# mLRStxtx.net
KiCad netlist of a schematic drawn in Altium Designer
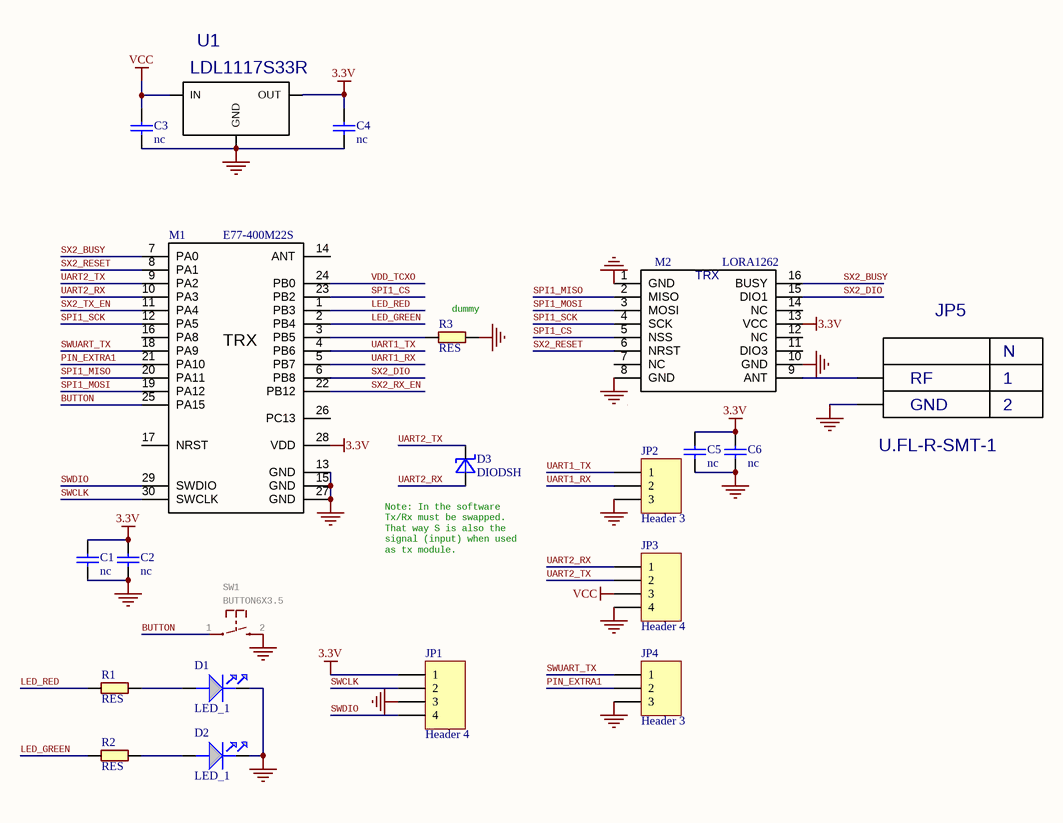
[diagram p0: mLRStxtx.SchDoc]

(export (version "E")
  (design (tool "Eeschema 10.0.6"))
  (components
    (comp (ref "C1")
      (value "nc")
      (footprint "C-0603")
      (fields (field (name "VOLTAGE") "50V"))
      (libsource (lib "LR1121EVM") (part "CAPN"))
    )
    (comp (ref "C2")
      (value "nc")
      (footprint "C-0603")
      (fields (field (name "VOLTAGE") "50V"))
      (libsource (lib "LR1121EVM") (part "CAPN"))
    )
    (comp (ref "C3")
      (value "nc")
      (footprint "C-0805")
      (fields (field (name "VOLTAGE") "50V"))
      (libsource (lib "LR1121EVM") (part "CAPN"))
    )
    (comp (ref "C4")
      (value "nc")
      (footprint "C-0805")
      (fields (field (name "VOLTAGE") "50V"))
      (libsource (lib "LR1121EVM") (part "CAPN"))
    )
    (comp (ref "C5")
      (value "nc")
      (footprint "C-0603")
      (fields (field (name "VOLTAGE") "50V"))
      (libsource (lib "LR1121EVM") (part "CAPN"))
    )
    (comp (ref "C6")
      (value "nc")
      (footprint "C-0603")
      (fields (field (name "VOLTAGE") "50V"))
      (libsource (lib "LR1121EVM") (part "CAPN"))
    )
    (comp (ref "D1") (value "LED_1") (footprint "LED_0805") (libsource (lib "Diodes") (part "LED_1")))
    (comp (ref "D2") (value "LED_1") (footprint "LED_0805") (libsource (lib "Diodes") (part "LED_1")))
    (comp (ref "D3") (value "DIODSH") (footprint "SOD-323") (libsource (lib "Diodes") (part "DIODSH")))
    (comp (ref "JP1")
      (value "Header 4")
      (footprint "HDR1X4")
      (description "Header, 4-Pin")
      (fields (field (name "PUBLISHER") "Altium Limited"))
      (libsource (lib "Miscellaneous Connectors") (part "Header 4"))
    )
    (comp (ref "JP2")
      (value "Header 3")
      (footprint "HDR1X3")
      (description "Header, 3-Pin")
      (fields (field (name "PUBLISHER") "Altium Limited"))
      (libsource (lib "Miscellaneous Connectors") (part "Header 3"))
    )
    (comp (ref "JP3")
      (value "Header 4")
      (footprint "HDR1X4")
      (description "Header, 4-Pin")
      (fields (field (name "PUBLISHER") "Altium Limited"))
      (libsource (lib "Miscellaneous Connectors") (part "Header 4"))
    )
    (comp (ref "JP4")
      (value "Header 3")
      (footprint "HDR1X3")
      (description "Header, 3-Pin")
      (fields (field (name "PUBLISHER") "Altium Limited"))
      (libsource (lib "Miscellaneous Connectors") (part "Header 3"))
    )
    (comp (ref "JP5")
      (value "U.FL-R-SMT-1")
      (footprint "U.FL-R-SMT-1")
      (libsource (lib "E2002") (part "U.FL-R-SMT-1"))
    )
    (comp (ref "M1")
      (value "E77-400M22S")
      (footprint "E77XX-M22")
      (libsource (lib "LR1121EVM") (part "E77-400M22S"))
    )
    (comp (ref "M2")
      (value "LORA1262")
      (footprint "LGA16_LORA1280")
      (libsource (lib "LR1121EVM") (part "LORA1262"))
    )
    (comp (ref "R1") (value "RES") (footprint "R-0603") (libsource (lib "LR1121EVM") (part "RES")))
    (comp (ref "R2") (value "RES") (footprint "R-0603") (libsource (lib "LR1121EVM") (part "RES")))
    (comp (ref "R3") (value "RES") (footprint "R-0603") (libsource (lib "LR1121EVM") (part "RES")))
    (comp (ref "SW1")
      (value "BUTTON6X3.5")
      (footprint "BUTTON-THT")
      (fields (field (name "LIBRARYNAME") "# stdlib"))
      (libsource (lib "# stdlib") (part "BUTTON6X3.5"))
    )
    (comp (ref "U1")
      (value "LDL1117S33R")
      (footprint "SOT223")
      (libsource (lib "E2002") (part "LDL1117S33R"))
    )
  )
  (nets
    (net (code "1") (name "/BUTTON") (class "Default")
      (node (ref "M1") (pin "25") (pinfunction "PA15_25") (pintype "passive"))
      (node (ref "SW1") (pin "1") (pinfunction "1_1") (pintype "passive"))
    )
    (net (code "2") (name "/LED_GREEN") (class "Default")
      (node (ref "M1") (pin "2") (pinfunction "PB4_2") (pintype "passive"))
      (node (ref "R2") (pin "2") (pinfunction "2_2") (pintype "passive"))
    )
    (net (code "3") (name "/LED_RED") (class "Default")
      (node (ref "M1") (pin "1") (pinfunction "PB3_1") (pintype "passive"))
      (node (ref "R1") (pin "2") (pinfunction "2_2") (pintype "passive"))
    )
    (net (code "4") (name "/PIN_EXTRA1") (class "Default")
      (node (ref "JP4") (pin "2") (pinfunction "2_2") (pintype "passive"))
      (node (ref "M1") (pin "21") (pinfunction "PA10_21") (pintype "passive"))
    )
    (net (code "5") (name "/SPI1_CS") (class "Default")
      (node (ref "M1") (pin "23") (pinfunction "PB2_23") (pintype "passive"))
      (node (ref "M2") (pin "5") (pinfunction "NSS_5") (pintype "passive"))
    )
    (net (code "6") (name "/SPI1_MISO") (class "Default")
      (node (ref "M1") (pin "20") (pinfunction "PA11_20") (pintype "passive"))
      (node (ref "M2") (pin "2") (pinfunction "MISO_2") (pintype "passive"))
    )
    (net (code "7") (name "/SPI1_MOSI") (class "Default")
      (node (ref "M1") (pin "19") (pinfunction "PA12_19") (pintype "passive"))
      (node (ref "M2") (pin "3") (pinfunction "MOSI_3") (pintype "passive"))
    )
    (net (code "8") (name "/SPI1_SCK") (class "Default")
      (node (ref "M1") (pin "12") (pinfunction "PA5_12") (pintype "passive"))
      (node (ref "M2") (pin "4") (pinfunction "SCK_4") (pintype "passive"))
    )
    (net (code "9") (name "/SWCLK") (class "Default")
      (node (ref "JP1") (pin "2") (pinfunction "2_2") (pintype "passive"))
      (node (ref "M1") (pin "30") (pinfunction "SWCLK_30") (pintype "passive"))
    )
    (net (code "10") (name "/SWDIO") (class "Default")
      (node (ref "JP1") (pin "4") (pinfunction "4_4") (pintype "passive"))
      (node (ref "M1") (pin "29") (pinfunction "SWDIO_29") (pintype "passive"))
    )
    (net (code "11") (name "/SWUART_TX") (class "Default")
      (node (ref "JP4") (pin "1") (pinfunction "1_1") (pintype "passive"))
      (node (ref "M1") (pin "18") (pinfunction "PA9_18") (pintype "passive"))
    )
    (net (code "12") (name "/SX2_BUSY") (class "Default")
      (node (ref "M1") (pin "7") (pinfunction "PA0_7") (pintype "passive"))
      (node (ref "M2") (pin "16") (pinfunction "BUSY_16") (pintype "passive"))
    )
    (net (code "13") (name "/SX2_DIO") (class "Default")
      (node (ref "M1") (pin "6") (pinfunction "PB8_6") (pintype "passive"))
      (node (ref "M2") (pin "15") (pinfunction "DIO1_15") (pintype "passive"))
    )
    (net (code "14") (name "/SX2_RESET") (class "Default")
      (node (ref "M1") (pin "8") (pinfunction "PA1_8") (pintype "passive"))
      (node (ref "M2") (pin "6") (pinfunction "NRST_6") (pintype "passive"))
    )
    (net (code "15") (name "/SX2_RX_EN") (class "Default")
      (node (ref "M1") (pin "22") (pinfunction "PB12_22") (pintype "passive"))
    )
    (net (code "16") (name "/SX2_TX_EN") (class "Default")
      (node (ref "M1") (pin "11") (pinfunction "PA4_11") (pintype "passive"))
    )
    (net (code "17") (name "/UART1_RX") (class "Default")
      (node (ref "JP2") (pin "2") (pinfunction "2_2") (pintype "passive"))
      (node (ref "M1") (pin "5") (pinfunction "PB7_5") (pintype "passive"))
    )
    (net (code "18") (name "/UART1_TX") (class "Default")
      (node (ref "JP2") (pin "1") (pinfunction "1_1") (pintype "passive"))
      (node (ref "M1") (pin "4") (pinfunction "PB6_4") (pintype "passive"))
    )
    (net (code "19") (name "/UART2_RX") (class "Default")
      (node (ref "D3") (pin "1") (pinfunction "1_1") (pintype "passive"))
      (node (ref "JP3") (pin "1") (pinfunction "1_1") (pintype "passive"))
      (node (ref "M1") (pin "10") (pinfunction "PA3_10") (pintype "passive"))
    )
    (net (code "20") (name "/UART2_TX") (class "Default")
      (node (ref "D3") (pin "2") (pinfunction "2_2") (pintype "passive"))
      (node (ref "JP3") (pin "2") (pinfunction "2_2") (pintype "passive"))
      (node (ref "M1") (pin "9") (pinfunction "PA2_9") (pintype "passive"))
    )
    (net (code "21") (name "/VDD_TCXO") (class "Default")
      (node (ref "M1") (pin "24") (pinfunction "PB0_24") (pintype "passive"))
    )
    (net (code "22") (name "3.3V") (class "Default")
      (node (ref "C1") (pin "1") (pinfunction "1_1") (pintype "passive"))
      (node (ref "C2") (pin "1") (pinfunction "1_1") (pintype "passive"))
      (node (ref "C4") (pin "1") (pinfunction "1_1") (pintype "passive"))
      (node (ref "C5") (pin "1") (pinfunction "1_1") (pintype "passive"))
      (node (ref "C6") (pin "1") (pinfunction "1_1") (pintype "passive"))
      (node (ref "JP1") (pin "1") (pinfunction "1_1") (pintype "passive"))
      (node (ref "M1") (pin "28") (pinfunction "VDD_28") (pintype "passive"))
      (node (ref "M2") (pin "13") (pinfunction "VCC_13") (pintype "passive"))
      (node (ref "U1") (pin "2") (pinfunction "OUT_2") (pintype "passive"))
    )
    (net (code "23") (name "GND") (class "Default")
      (node (ref "C1") (pin "2") (pinfunction "2_2") (pintype "passive"))
      (node (ref "C2") (pin "2") (pinfunction "2_2") (pintype "passive"))
      (node (ref "C3") (pin "2") (pinfunction "2_2") (pintype "passive"))
      (node (ref "C4") (pin "2") (pinfunction "2_2") (pintype "passive"))
      (node (ref "C5") (pin "2") (pinfunction "2_2") (pintype "passive"))
      (node (ref "C6") (pin "2") (pinfunction "2_2") (pintype "passive"))
      (node (ref "D1") (pin "K") (pinfunction "CATHODE_K") (pintype "passive"))
      (node (ref "D2") (pin "K") (pinfunction "CATHODE_K") (pintype "passive"))
      (node (ref "JP1") (pin "3") (pinfunction "3_3") (pintype "passive"))
      (node (ref "JP2") (pin "3") (pinfunction "3_3") (pintype "passive"))
      (node (ref "JP3") (pin "4") (pinfunction "4_4") (pintype "passive"))
      (node (ref "JP4") (pin "3") (pinfunction "3_3") (pintype "passive"))
      (node (ref "JP5") (pin "2") (pinfunction "2_2") (pintype "passive"))
      (node (ref "M1") (pin "13") (pinfunction "GND_13") (pintype "passive"))
      (node (ref "M1") (pin "15") (pinfunction "GND_15") (pintype "passive"))
      (node (ref "M1") (pin "27") (pinfunction "GND_27") (pintype "passive"))
      (node (ref "M2") (pin "1") (pinfunction "GND_1") (pintype "passive"))
      (node (ref "M2") (pin "10") (pinfunction "GND_10") (pintype "passive"))
      (node (ref "M2") (pin "8") (pinfunction "GND_8") (pintype "passive"))
      (node (ref "R3") (pin "1") (pinfunction "1_1") (pintype "passive"))
      (node (ref "SW1") (pin "2") (pinfunction "3_2") (pintype "passive"))
      (node (ref "U1") (pin "1") (pinfunction "GND_1") (pintype "passive"))
    )
    (net (code "24") (name "Net-(D1-ANODE)") (class "Default")
      (node (ref "D1") (pin "A") (pinfunction "ANODE_A") (pintype "passive"))
      (node (ref "R1") (pin "1") (pinfunction "1_1") (pintype "passive"))
    )
    (net (code "25") (name "Net-(D2-ANODE)") (class "Default")
      (node (ref "D2") (pin "A") (pinfunction "ANODE_A") (pintype "passive"))
      (node (ref "R2") (pin "1") (pinfunction "1_1") (pintype "passive"))
    )
    (net (code "26") (name "Net-(M1-PB5)") (class "Default")
      (node (ref "M1") (pin "3") (pinfunction "PB5_3") (pintype "passive"))
      (node (ref "R3") (pin "2") (pinfunction "2_2") (pintype "passive"))
    )
    (net (code "27") (name "Net-(M2-ANT)") (class "Default")
      (node (ref "JP5") (pin "1") (pinfunction "1_1") (pintype "passive"))
      (node (ref "M2") (pin "9") (pinfunction "ANT_9") (pintype "passive"))
    )
    (net (code "28") (name "VCC") (class "Default")
      (node (ref "C3") (pin "1") (pinfunction "1_1") (pintype "passive"))
      (node (ref "JP3") (pin "3") (pinfunction "3_3") (pintype "passive"))
      (node (ref "U1") (pin "3") (pinfunction "IN_3") (pintype "passive"))
    )
    (net (code "29") (name "unconnected-(M1-ANT-Pad14)") (class "Default")
      (node (ref "M1") (pin "14") (pinfunction "ANT_14") (pintype "passive"))
    )
    (net (code "30") (name "unconnected-(M1-NRST-Pad17)") (class "Default")
      (node (ref "M1") (pin "17") (pinfunction "NRST_17") (pintype "passive"))
    )
    (net (code "31") (name "unconnected-(M1-PA8-Pad16)") (class "Default")
      (node (ref "M1") (pin "16") (pinfunction "PA8_16") (pintype "passive"))
    )
    (net (code "32") (name "unconnected-(M1-PC13-Pad26)") (class "Default")
      (node (ref "M1") (pin "26") (pinfunction "PC13_26") (pintype "passive"))
    )
    (net (code "33") (name "unconnected-(M2-DIO3-Pad11)") (class "Default")
      (node (ref "M2") (pin "11") (pinfunction "DIO3_11") (pintype "passive"))
    )
    (net (code "34") (name "unconnected-(M2-NC-Pad7)") (class "Default")
      (node (ref "M2") (pin "7") (pinfunction "NC_7") (pintype "passive"))
    )
    (net (code "35") (name "unconnected-(M2-NC-Pad12)") (class "Default")
      (node (ref "M2") (pin "12") (pinfunction "NC_12") (pintype "passive"))
    )
    (net (code "36") (name "unconnected-(M2-NC-Pad14)") (class "Default")
      (node (ref "M2") (pin "14") (pinfunction "NC_14") (pintype "passive"))
    )
    (net (code "37") (name "unconnected-(U1-Pad4)") (class "Default")
      (node (ref "U1") (pin "4") (pintype "passive"))
    )
  )
)
